# H_Bridge_Driver.net
KiCad netlist of a schematic drawn in Altium Designer
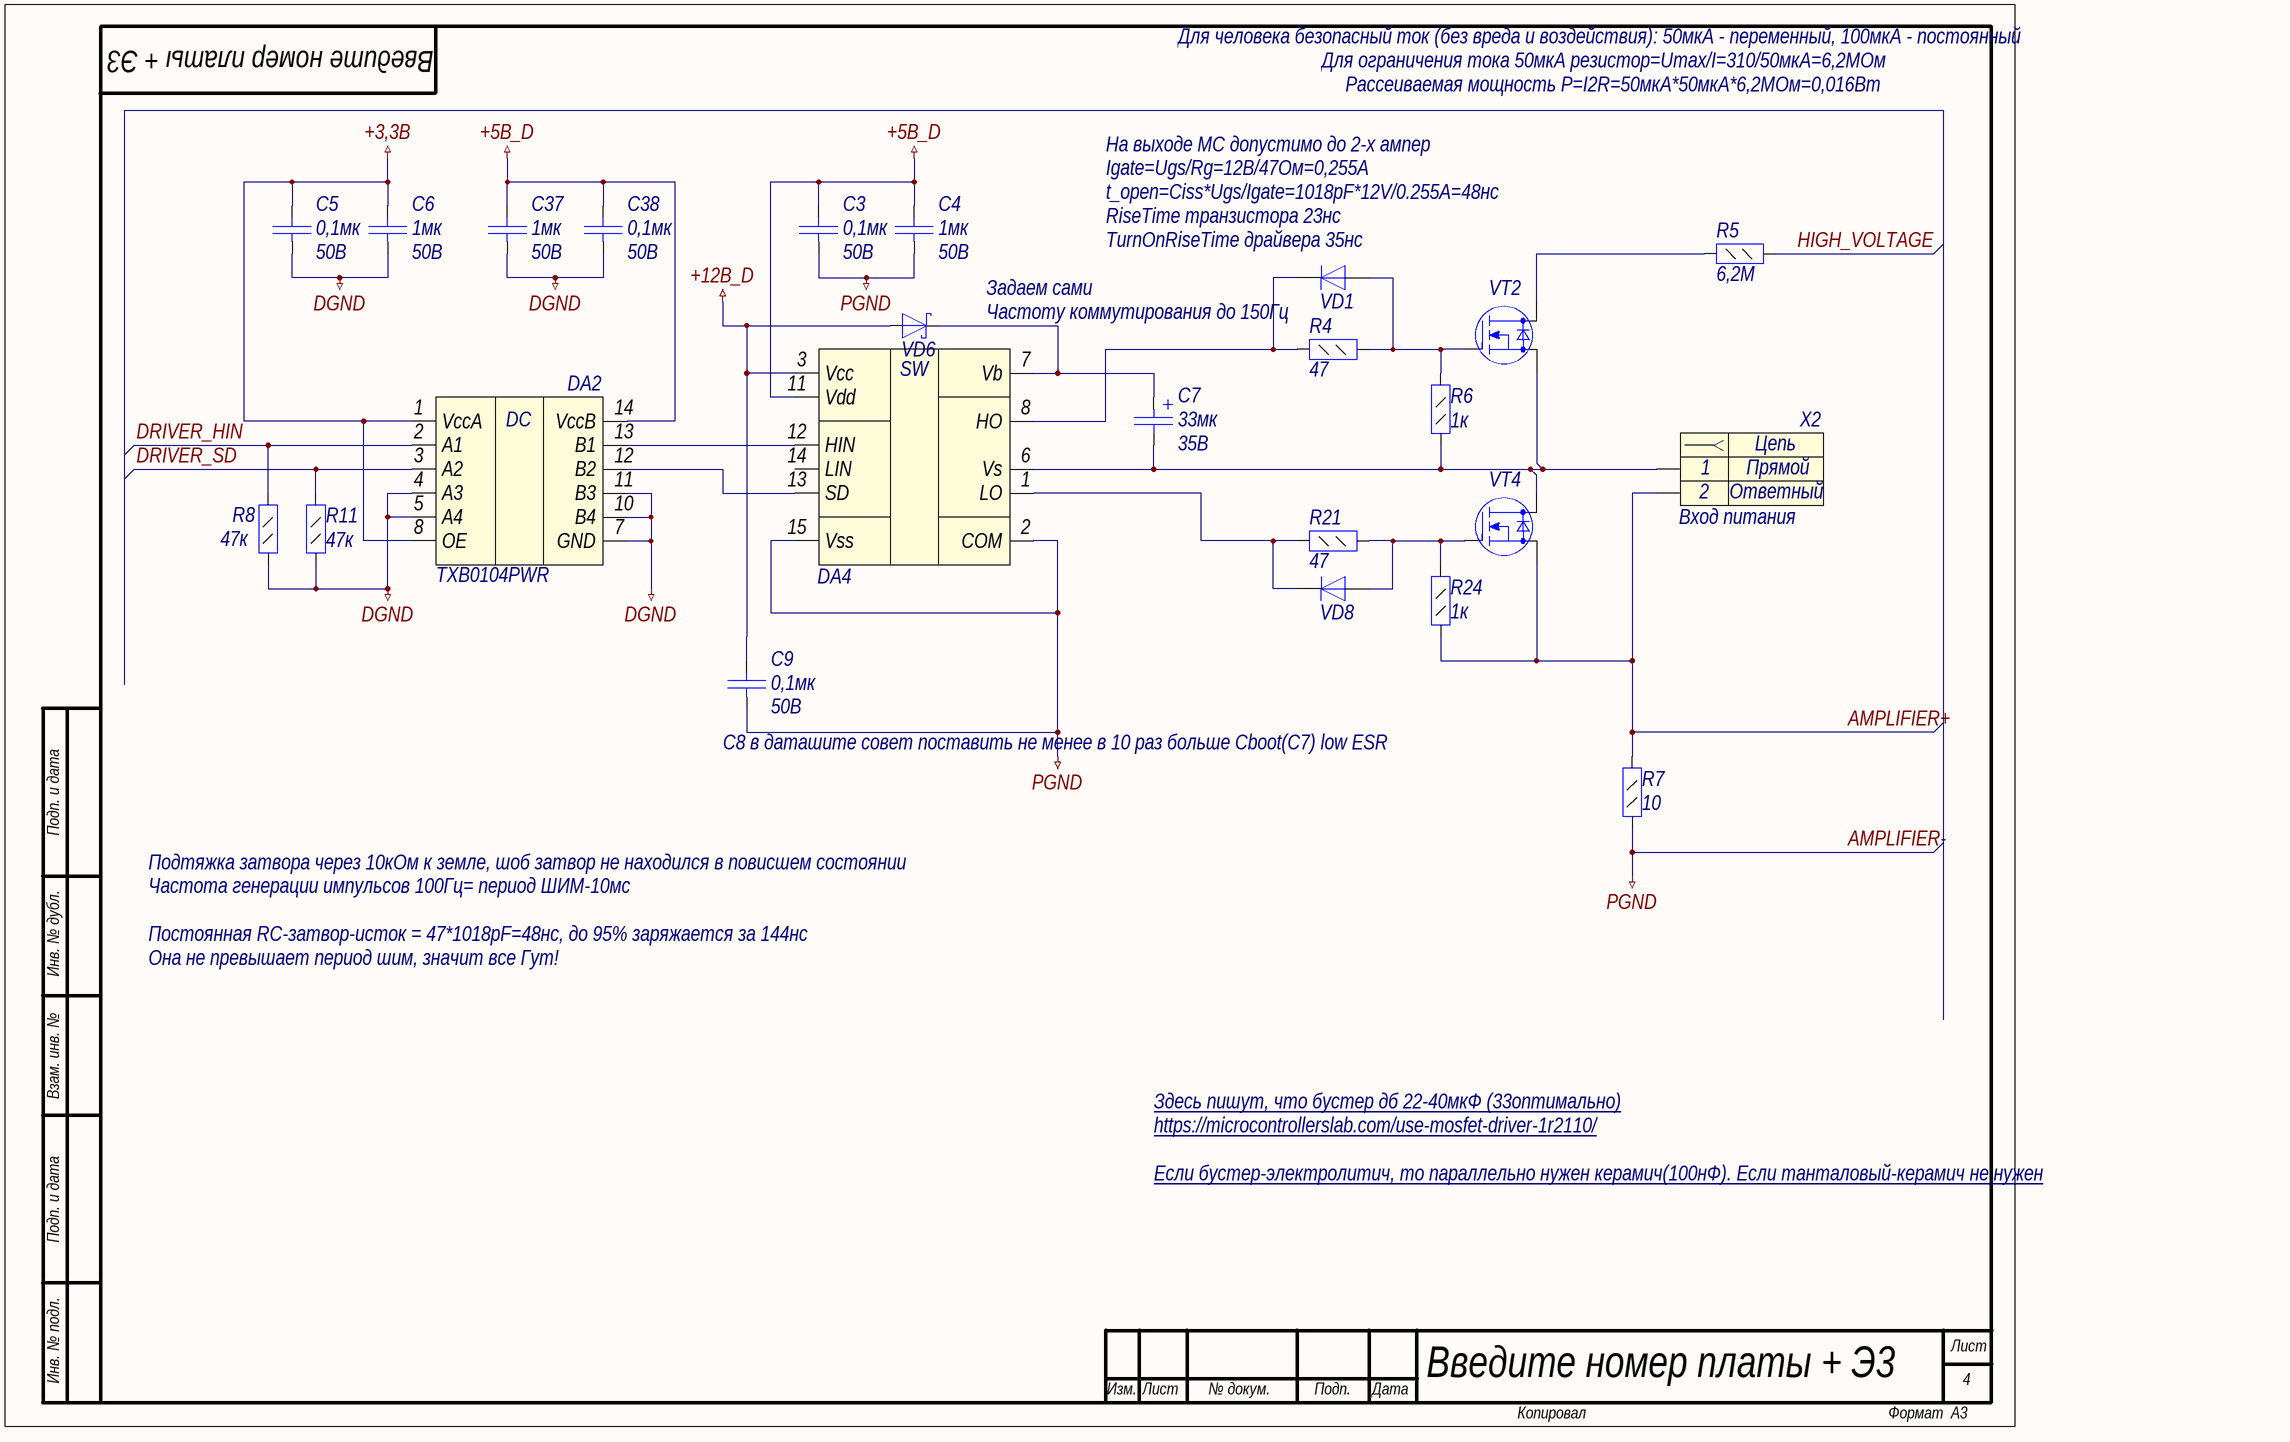
[diagram p0: H_Bridge_Driver.SchDoc]

(export (version "E")
  (design (tool "Eeschema 10.0.6"))
  (components
    (comp (ref "C3")
      (value "0,1мк")
      (footprint "C0805")
      (description "Конденсатор")
      (fields
        (field (name "VOLTAGE") "50В")
        (field (name "PART NUMBER") "GRM21BR71H104KA01L ")
        (field (name "Comment") "Capacitor")
      )
      (libsource (lib "MOP44") (part "Capacitor"))
    )
    (comp (ref "C4")
      (value "1мк")
      (footprint "C0805")
      (description "Конденсатор")
      (fields
        (field (name "VOLTAGE") "50B")
        (field (name "PART NUMBER") "GRM21BR71H105K")
        (field (name "Comment") "Capacitor")
      )
      (libsource (lib "MOP44") (part "Capacitor"))
    )
    (comp (ref "C5")
      (value "0,1мк")
      (footprint "C0805")
      (description "Конденсатор")
      (fields
        (field (name "VOLTAGE") "50В")
        (field (name "PART NUMBER") "GRM21BR71H104KA01L ")
        (field (name "Comment") "Capacitor")
      )
      (libsource (lib "MOP44") (part "Capacitor"))
    )
    (comp (ref "C6")
      (value "1мк")
      (footprint "C0805")
      (description "Конденсатор")
      (fields
        (field (name "VOLTAGE") "50B")
        (field (name "PART NUMBER") "GRM21BR71H105K")
        (field (name "Comment") "Capacitor")
      )
      (libsource (lib "MOP44") (part "Capacitor"))
    )
    (comp (ref "C7")
      (value "33мк")
      (footprint "TANTAL CASE D")
      (description "Конденсатор полярный")
      (fields
        (field (name "VOLTAGE") "35В")
        (field (name "PART NUMBER") "TAJD336K035RNJ")
        (field (name "Comment") "Capacitor_pol")
      )
      (libsource (lib "MOP44") (part "Capacitor_pol"))
    )
    (comp (ref "C9")
      (value "0,1мк")
      (footprint "C0805")
      (description "Конденсатор")
      (fields
        (field (name "VOLTAGE") "50В")
        (field (name "PART NUMBER") "GRM21BR71H104KA01L ")
        (field (name "Comment") "Capacitor")
      )
      (libsource (lib "MOP44") (part "Capacitor"))
    )
    (comp (ref "C37")
      (value "1мк")
      (footprint "C0805")
      (description "Конденсатор")
      (fields
        (field (name "VOLTAGE") "50B")
        (field (name "PART NUMBER") "GRM21BR71H105K")
        (field (name "Comment") "Capacitor")
      )
      (libsource (lib "MOP44") (part "Capacitor"))
    )
    (comp (ref "C38")
      (value "0,1мк")
      (footprint "C0805")
      (description "Конденсатор")
      (fields
        (field (name "VOLTAGE") "50В")
        (field (name "PART NUMBER") "GRM21BR71H104KA01L ")
        (field (name "Comment") "Capacitor")
      )
      (libsource (lib "MOP44") (part "Capacitor"))
    )
    (comp (ref "DA2")
      (value "TXB0104")
      (footprint "TSSOP14")
      (description "4-Bit Bidirectional Voltage-level Translator")
      (fields (field (name "PART NUMBER") "TXB0104PWR") (field (name "MANUFACTURER") "Texas Instruments"))
      (libsource (lib "MOP44") (part "TXB0104"))
    )
    (comp (ref "DA4")
      (value "IR2110S")
      (footprint "SO16")
      (description "High and Low Side Driver")
      (fields (field (name "PART NUMBER") "IR2110STRPBF"))
      (libsource (lib "MOP44") (part "IR2110S"))
    )
    (comp (ref "R4")
      (value "47")
      (footprint "R0805")
      (description "Резистор")
      (fields (field (name "PART NUMBER") "RC0805FR-0747RL") (field (name "POWER") "0,125Вт"))
      (libsource (lib "MOP44") (part "Resistor_0,125Вт"))
    )
    (comp (ref "R5")
      (value "6,2М")
      (footprint "R0805")
      (description "Резистор")
      (fields (field (name "PART NUMBER") "RC0805FR-076M2") (field (name "POWER") "0,125Вт"))
      (libsource (lib "MOP44") (part "Resistor_0,125Вт"))
    )
    (comp (ref "R6")
      (value "1к")
      (footprint "R0805")
      (description "Резистор")
      (fields (field (name "PART NUMBER") "RC0805FR-071KL") (field (name "POWER") "0,125Вт"))
      (libsource (lib "") (part "Resistor_0,125Вт_1"))
    )
    (comp (ref "R7")
      (value "10")
      (footprint "R0805")
      (description "Резистор")
      (fields (field (name "PART NUMBER") "RC0805FR-0710RL") (field (name "POWER") "0,125Вт"))
      (libsource (lib "") (part "Resistor_0,125Вт_1"))
    )
    (comp (ref "R8")
      (value "47к")
      (footprint "R0805")
      (description "Резистор")
      (fields (field (name "PART NUMBER") "RC0805FR-0747KL") (field (name "POWER") "0,125Вт"))
      (libsource (lib "") (part "Resistor_0,125Вт_1"))
    )
    (comp (ref "R11")
      (value "47к")
      (footprint "R0805")
      (description "Резистор")
      (fields (field (name "PART NUMBER") "RC0805FR-0747KL") (field (name "POWER") "0,125Вт"))
      (libsource (lib "") (part "Resistor_0,125Вт_1"))
    )
    (comp (ref "R21")
      (value "47")
      (footprint "R1206")
      (description "Резистор")
      (fields (field (name "PART NUMBER") "RC0805FR-0747RL") (field (name "POWER") "0,125Вт"))
      (libsource (lib "MOP44") (part "Resistor_0,125Вт"))
    )
    (comp (ref "R24")
      (value "1к")
      (footprint "R0805")
      (description "Резистор")
      (fields (field (name "PART NUMBER") "RC0805FR-071KL") (field (name "POWER") "0,125Вт"))
      (libsource (lib "") (part "Resistor_0,125Вт_1"))
    )
    (comp (ref "VD1")
      (value "Diode")
      (footprint "SMA")
      (description "Диод")
      (fields (field (name "PART NUMBER") "SMA4007"))
      (libsource (lib "MOP44") (part "Diode"))
    )
    (comp (ref "VD6")
      (value "DiodeSchottky")
      (footprint "SMA")
      (description "Диод Шоттки")
      (fields (field (name "PART NUMBER") "SK34A"))
      (libsource (lib "MOP44") (part "DiodeSchottky"))
    )
    (comp (ref "VD8")
      (value "Diode")
      (footprint "SMA")
      (description "Диод")
      (fields (field (name "PART NUMBER") "SMA4007"))
      (libsource (lib "MOP44") (part "Diode"))
    )
    (comp (ref "VT2")
      (value "N-MOSFET")
      (footprint "D2PAK")
      (fields (field (name "PART NUMBER") "IRF840ASPBF") (field (name "MANUFACTURER") "Vishay"))
      (libsource (lib "MOP44") (part "N-MOSFET"))
    )
    (comp (ref "VT4")
      (value "N-MOSFET")
      (footprint "D2PAK")
      (fields (field (name "PART NUMBER") "IRF840ASPBF") (field (name "MANUFACTURER") "Vishay"))
      (libsource (lib "MOP44") (part "N-MOSFET"))
    )
    (comp (ref "X2")
      (value "Вход питания")
      (footprint "CWF-2R")
      (description "Разъем - 2 конт. розетка")
      (fields (field (name "PART NUMBER") "DS1069-2 MR-A"))
      (libsource (lib "MOP44") (part "Header_2_sct"))
    )
  )
  (nets
    (net (code "1") (name "+3,3В") (class "Default")
      (node (ref "C5") (pin "2") (pinfunction "2_2") (pintype "passive"))
      (node (ref "C6") (pin "2") (pinfunction "2_2") (pintype "passive"))
      (node (ref "DA2") (pin "1") (pinfunction "VccA_1") (pintype "power_in"))
      (node (ref "DA2") (pin "8") (pinfunction "OE_8") (pintype "power_in"))
    )
    (net (code "2") (name "+5B_D") (class "Default")
      (node (ref "C3") (pin "2") (pinfunction "2_2") (pintype "passive"))
      (node (ref "C37") (pin "2") (pinfunction "2_2") (pintype "passive"))
      (node (ref "C38") (pin "2") (pinfunction "2_2") (pintype "passive"))
      (node (ref "C4") (pin "2") (pinfunction "2_2") (pintype "passive"))
      (node (ref "DA2") (pin "14") (pinfunction "VccB_14") (pintype "power_in"))
      (node (ref "DA4") (pin "11") (pinfunction "Vdd_11") (pintype "passive"))
    )
    (net (code "3") (name "+12В_D") (class "Default")
      (node (ref "C9") (pin "2") (pinfunction "2_2") (pintype "passive"))
      (node (ref "DA4") (pin "3") (pinfunction "Vcc_3") (pintype "passive"))
      (node (ref "VD6") (pin "2") (pinfunction "A_2") (pintype "passive"))
    )
    (net (code "4") (name "/AMPLIFIER+") (class "Default")
      (node (ref "R24") (pin "1") (pinfunction "1_1") (pintype "passive"))
      (node (ref "R7") (pin "2") (pinfunction "2_2") (pintype "passive"))
      (node (ref "VT4") (pin "3") (pinfunction "S_3") (pintype "passive"))
      (node (ref "X2") (pin "2") (pinfunction "2_2") (pintype "passive"))
    )
    (net (code "5") (name "/DRIVER_HIN") (class "Default")
      (node (ref "DA2") (pin "2") (pinfunction "A1_2") (pintype "power_in"))
      (node (ref "R8") (pin "2") (pinfunction "2_2") (pintype "passive"))
    )
    (net (code "6") (name "/DRIVER_SD") (class "Default")
      (node (ref "DA2") (pin "3") (pinfunction "A2_3") (pintype "power_in"))
      (node (ref "R11") (pin "2") (pinfunction "2_2") (pintype "passive"))
    )
    (net (code "7") (name "/HIGH_VOLTAGE") (class "Default")
      (node (ref "R5") (pin "2") (pinfunction "2_2") (pintype "passive"))
    )
    (net (code "8") (name "DGND") (class "Default")
      (node (ref "C37") (pin "1") (pinfunction "1_1") (pintype "passive"))
      (node (ref "C38") (pin "1") (pinfunction "1_1") (pintype "passive"))
      (node (ref "C5") (pin "1") (pinfunction "1_1") (pintype "passive"))
      (node (ref "C6") (pin "1") (pinfunction "1_1") (pintype "passive"))
      (node (ref "DA2") (pin "10") (pinfunction "B4_10") (pintype "power_in"))
      (node (ref "DA2") (pin "11") (pinfunction "B3_11") (pintype "power_in"))
      (node (ref "DA2") (pin "4") (pinfunction "A3_4") (pintype "power_in"))
      (node (ref "DA2") (pin "5") (pinfunction "A4_5") (pintype "power_in"))
      (node (ref "DA2") (pin "7") (pinfunction "GND_7") (pintype "power_in"))
      (node (ref "R11") (pin "1") (pinfunction "1_1") (pintype "passive"))
      (node (ref "R8") (pin "1") (pinfunction "1_1") (pintype "passive"))
    )
    (net (code "9") (name "Net-(DA2-B1)") (class "Default")
      (node (ref "DA2") (pin "13") (pinfunction "B1_13") (pintype "power_in"))
      (node (ref "DA4") (pin "12") (pinfunction "HIN_12") (pintype "passive"))
    )
    (net (code "10") (name "Net-(DA2-B2)") (class "Default")
      (node (ref "DA2") (pin "12") (pinfunction "B2_12") (pintype "power_in"))
      (node (ref "DA4") (pin "13") (pinfunction "SD_13") (pintype "passive"))
    )
    (net (code "11") (name "Net-(DA4-HO)") (class "Default")
      (node (ref "DA4") (pin "8") (pinfunction "HO_8") (pintype "passive"))
      (node (ref "R4") (pin "1") (pinfunction "1_1") (pintype "passive"))
      (node (ref "VD1") (pin "1") (pinfunction "K_1") (pintype "passive"))
    )
    (net (code "12") (name "Net-(DA4-LO)") (class "Default")
      (node (ref "DA4") (pin "1") (pinfunction "LO_1") (pintype "passive"))
      (node (ref "R21") (pin "1") (pinfunction "1_1") (pintype "passive"))
      (node (ref "VD8") (pin "1") (pinfunction "K_1") (pintype "passive"))
    )
    (net (code "13") (name "Net-(DA4-Vb)") (class "Default")
      (node (ref "C7") (pin "1") (pinfunction "1_1") (pintype "passive"))
      (node (ref "DA4") (pin "7") (pinfunction "Vb_7") (pintype "passive"))
      (node (ref "VD6") (pin "1") (pinfunction "K_1") (pintype "passive"))
    )
    (net (code "14") (name "Net-(DA4-Vs)") (class "Default")
      (node (ref "C7") (pin "2") (pinfunction "2_2") (pintype "passive"))
      (node (ref "DA4") (pin "6") (pinfunction "Vs_6") (pintype "passive"))
      (node (ref "R6") (pin "1") (pinfunction "1_1") (pintype "passive"))
      (node (ref "VT2") (pin "3") (pinfunction "S_3") (pintype "passive"))
      (node (ref "VT4") (pin "2") (pinfunction "D_2") (pintype "passive"))
      (node (ref "X2") (pin "1") (pinfunction "1_1") (pintype "passive"))
    )
    (net (code "15") (name "Net-(VD1-A)") (class "Default")
      (node (ref "R4") (pin "2") (pinfunction "2_2") (pintype "passive"))
      (node (ref "R6") (pin "2") (pinfunction "2_2") (pintype "passive"))
      (node (ref "VD1") (pin "2") (pinfunction "A_2") (pintype "passive"))
      (node (ref "VT2") (pin "1") (pinfunction "G_1") (pintype "passive"))
    )
    (net (code "16") (name "Net-(VD8-A)") (class "Default")
      (node (ref "R21") (pin "2") (pinfunction "2_2") (pintype "passive"))
      (node (ref "R24") (pin "2") (pinfunction "2_2") (pintype "passive"))
      (node (ref "VD8") (pin "2") (pinfunction "A_2") (pintype "passive"))
      (node (ref "VT4") (pin "1") (pinfunction "G_1") (pintype "passive"))
    )
    (net (code "17") (name "Net-(VT2-D)") (class "Default")
      (node (ref "R5") (pin "1") (pinfunction "1_1") (pintype "passive"))
      (node (ref "VT2") (pin "2") (pinfunction "D_2") (pintype "passive"))
    )
    (net (code "18") (name "PGND") (class "Default")
      (node (ref "C3") (pin "1") (pinfunction "1_1") (pintype "passive"))
      (node (ref "C4") (pin "1") (pinfunction "1_1") (pintype "passive"))
      (node (ref "C9") (pin "1") (pinfunction "1_1") (pintype "passive"))
      (node (ref "DA4") (pin "15") (pinfunction "Vss_15") (pintype "passive"))
      (node (ref "DA4") (pin "2") (pinfunction "COM_2") (pintype "passive"))
      (node (ref "R7") (pin "1") (pinfunction "1_1") (pintype "passive"))
    )
    (net (code "19") (name "unconnected-(DA4-LIN-Pad14)") (class "Default")
      (node (ref "DA4") (pin "14") (pinfunction "LIN_14") (pintype "passive"))
    )
  )
)
